# SCH_Cameron_PCB_2022-05-20.net
KiCad netlist of a schematic drawn in EasyEDA
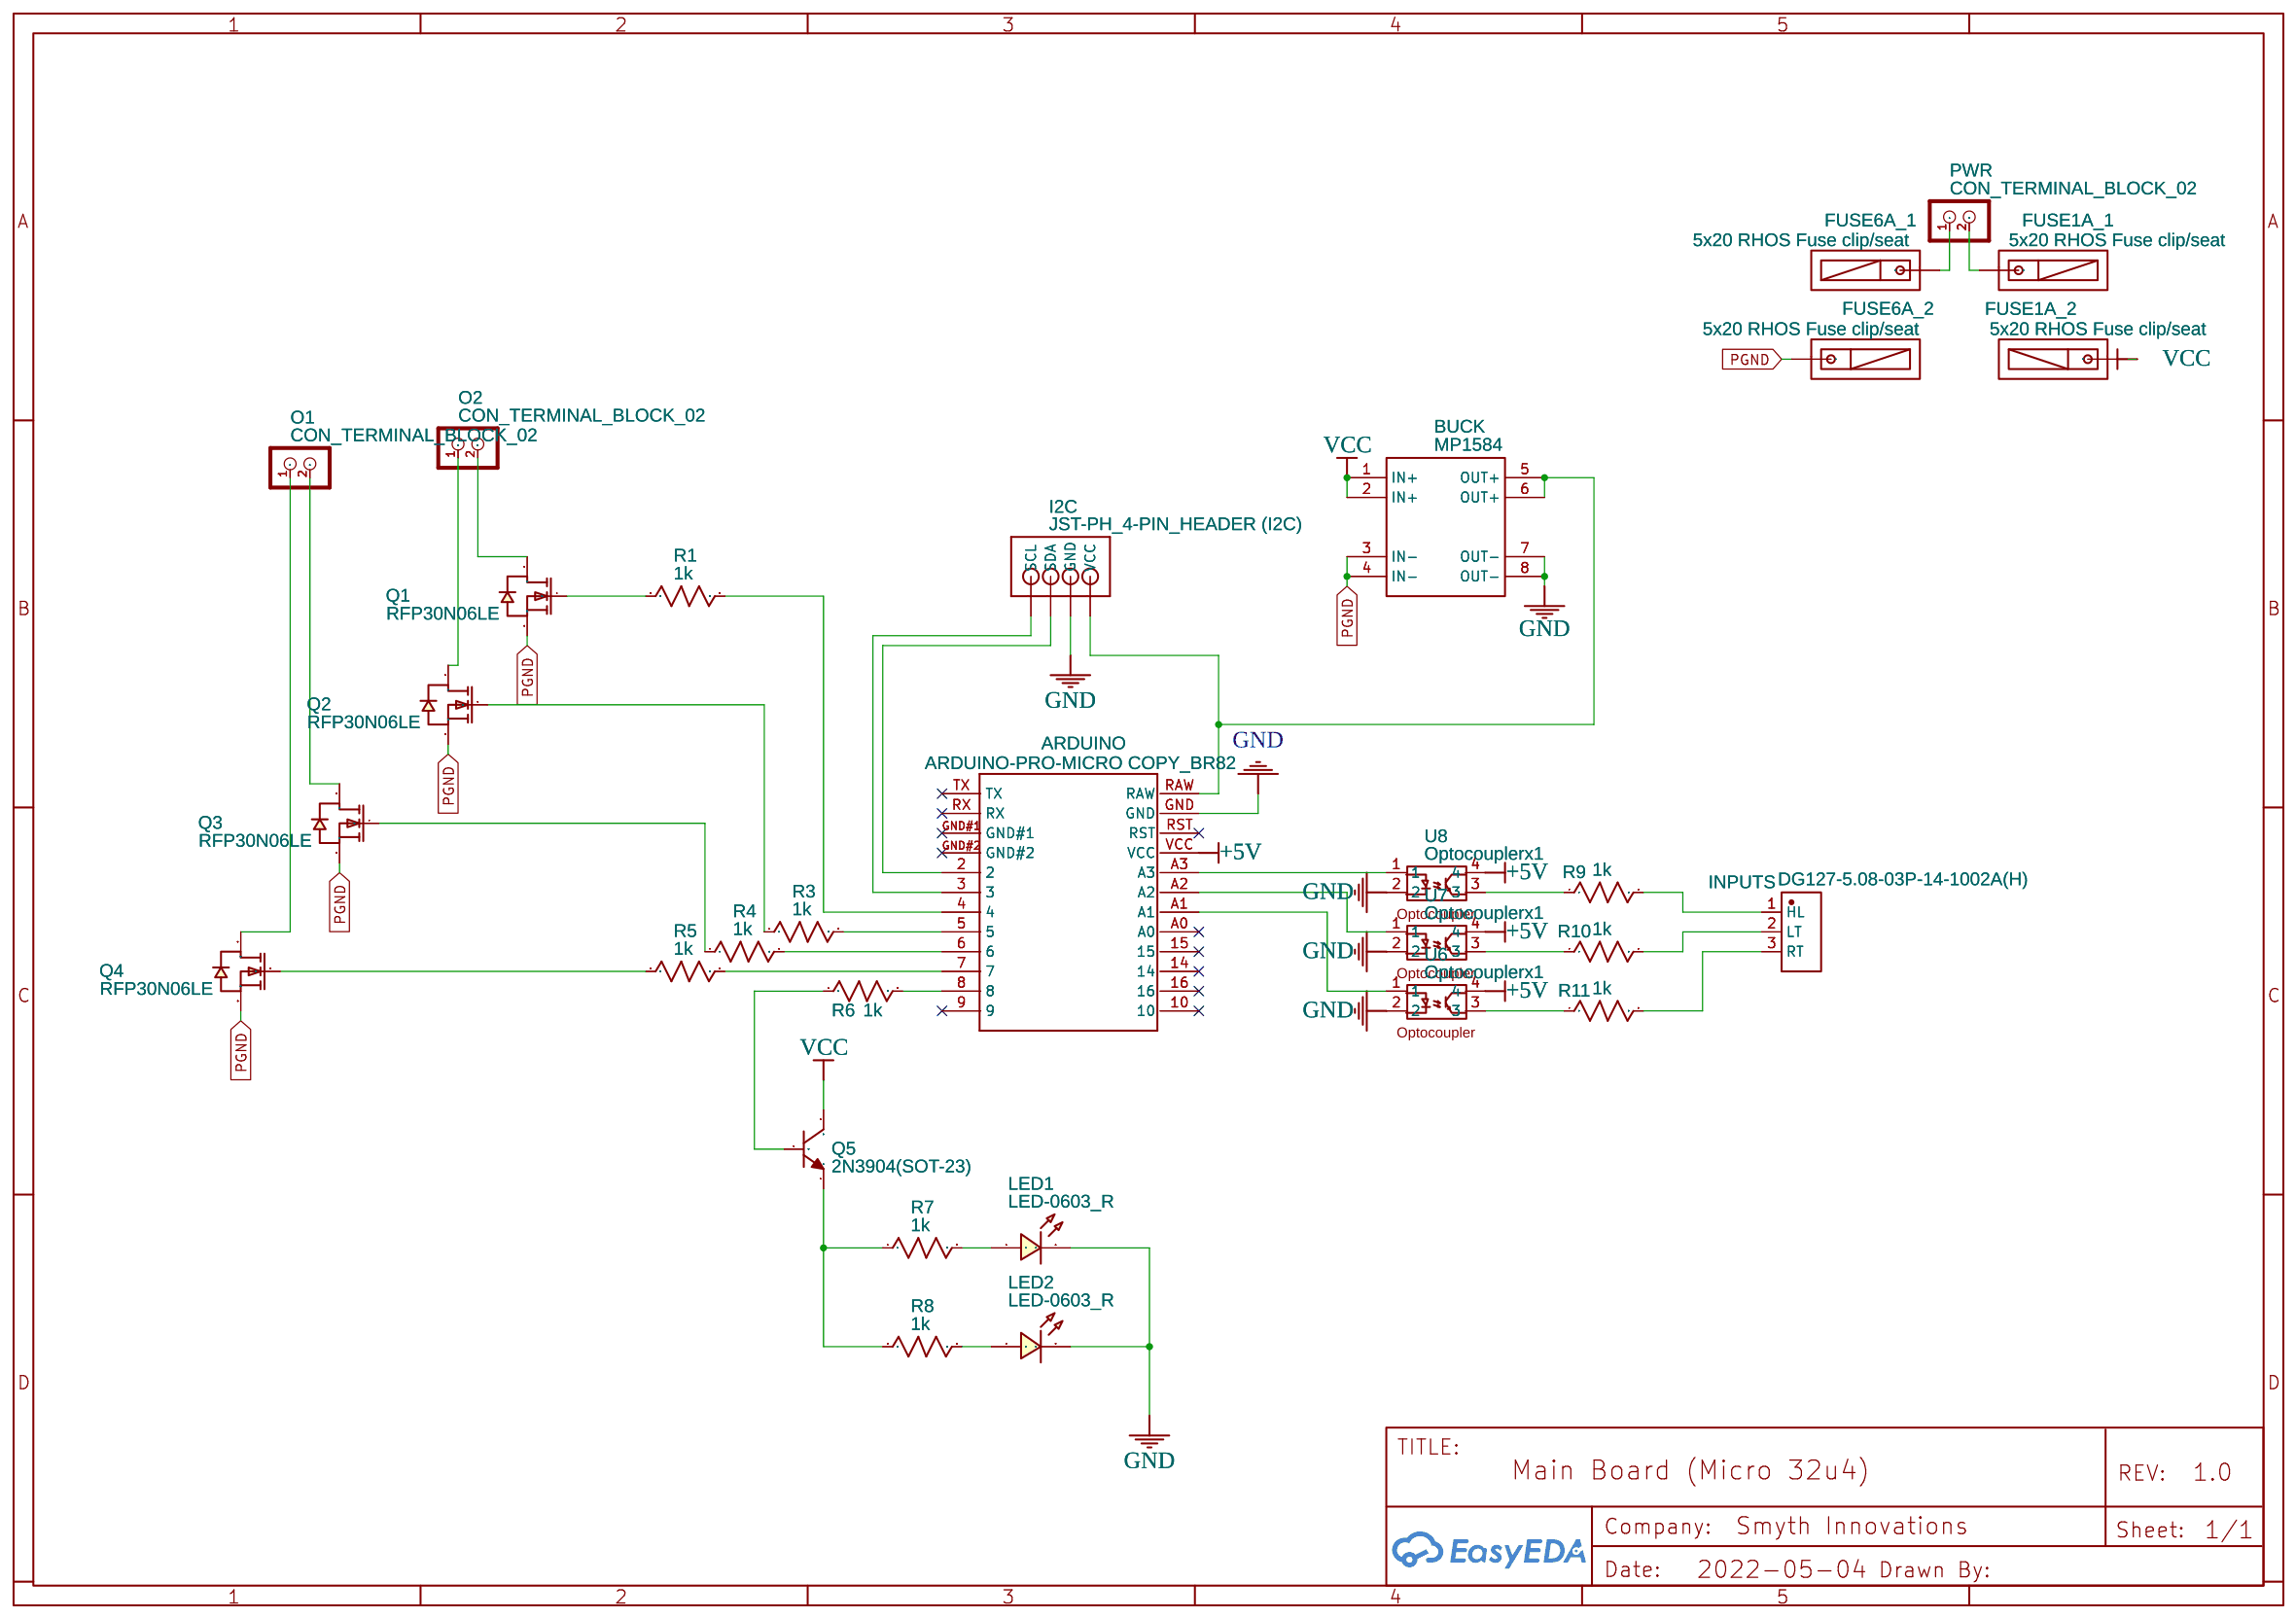
[diagram p0: schematic sheet]

(export (version "E")
  (design (tool "Eeschema 10.0.6"))
  (components
    (comp (ref "ARDUINO")
      (value "ARDUINO-PRO-MICRO COPY_BR82")
      (libsource (lib "") (part "ARDUINO-PRO-MICRO COPY_BR82"))
    )
    (comp (ref "BUCK") (value "MP1584") (libsource (lib "") (part "MP1584")))
    (comp (ref "FUSE1A_1")
      (value "5x20 RHOS Fuse clip/seat")
      (fields (field (name "BOM_Supplier Part") "C3130"))
      (libsource (lib "") (part "5x20 RHOS Fuse clip/seat_2"))
    )
    (comp (ref "FUSE1A_2")
      (value "5x20 RHOS Fuse clip/seat")
      (fields (field (name "BOM_Supplier Part") "C3130"))
      (libsource (lib "") (part "5x20 RHOS Fuse clip/seat_3"))
    )
    (comp (ref "FUSE6A_1")
      (value "5x20 RHOS Fuse clip/seat")
      (fields (field (name "BOM_Supplier Part") "C3130"))
      (libsource (lib "") (part "5x20 RHOS Fuse clip/seat_1"))
    )
    (comp (ref "FUSE6A_2")
      (value "5x20 RHOS Fuse clip/seat")
      (fields (field (name "BOM_Supplier Part") "C3130"))
      (libsource (lib "") (part "5x20 RHOS Fuse clip/seat"))
    )
    (comp (ref "I2C") (value "JST-PH_4-PIN_HEADER (I2C)") (libsource (lib "") (part "JST-PH_4-PIN_HEADER")))
    (comp (ref "INPUTS")
      (value "DG127-5.08-03P-14-1002A(H)")
      (fields (field (name "BOM_Supplier Part") "C669321"))
      (libsource (lib "") (part "DG127-5.08-03P-14-1002A(H)"))
    )
    (comp (ref "LED1")
      (value "LED-0603_R")
      (fields
        (field (name "BOM_Manufacturer Part") "19-217/R6C-AL1M2VY/3T")
        (field (name "BOM_Supplier Part") "C72044")
      )
      (libsource (lib "") (part "LED-0603_R"))
    )
    (comp (ref "LED2")
      (value "LED-0603_R")
      (fields
        (field (name "BOM_Manufacturer Part") "19-217/R6C-AL1M2VY/3T")
        (field (name "BOM_Supplier Part") "C72044")
      )
      (libsource (lib "") (part "LED-0603_R"))
    )
    (comp (ref "O1") (value "CON_TERMINAL_BLOCK_02") (libsource (lib "") (part "CON_TERMINAL_BLOCK_02")))
    (comp (ref "O2") (value "CON_TERMINAL_BLOCK_02") (libsource (lib "") (part "CON_TERMINAL_BLOCK_02")))
    (comp (ref "PWR") (value "CON_TERMINAL_BLOCK_02") (libsource (lib "") (part "CON_TERMINAL_BLOCK_02_1")))
    (comp (ref "Q1")
      (value "RFP30N06LE")
      (fields (field (name "BOM_Supplier Part") "C878812"))
      (libsource (lib "") (part "RFP30N06LE"))
    )
    (comp (ref "Q2")
      (value "RFP30N06LE")
      (fields (field (name "BOM_Supplier Part") "C878812"))
      (libsource (lib "") (part "RFP30N06LE"))
    )
    (comp (ref "Q3")
      (value "RFP30N06LE")
      (fields (field (name "BOM_Supplier Part") "C878812"))
      (libsource (lib "") (part "RFP30N06LE"))
    )
    (comp (ref "Q4")
      (value "RFP30N06LE")
      (fields (field (name "BOM_Supplier Part") "C878812"))
      (libsource (lib "") (part "RFP30N06LE"))
    )
    (comp (ref "Q5")
      (value "2N3904(SOT-23)")
      (fields
        (field (name "BOM_Manufacturer Part") "2n3904S-RTK/PS")
        (field (name "BOM_Supplier Part") "C18536")
      )
      (libsource (lib "") (part "2N3904(SOT-23)"))
    )
    (comp (ref "R1") (value "1k") (libsource (lib "") (part "R_AXIAL-0.3_US")))
    (comp (ref "R3") (value "1k") (libsource (lib "") (part "R_0603_US")))
    (comp (ref "R4") (value "1k") (libsource (lib "") (part "R_0603_US")))
    (comp (ref "R5") (value "1k") (libsource (lib "") (part "R_0603_US")))
    (comp (ref "R6") (value "1k") (libsource (lib "") (part "R_0603_US")))
    (comp (ref "R7") (value "1k") (libsource (lib "") (part "R_0603_US")))
    (comp (ref "R8") (value "1k") (libsource (lib "") (part "R_0603_US")))
    (comp (ref "R9") (value "1k") (libsource (lib "") (part "R_0603_US")))
    (comp (ref "R10") (value "1k") (libsource (lib "") (part "R_0603_US")))
    (comp (ref "R11") (value "1k") (libsource (lib "") (part "R_0603_US")))
    (comp (ref "U6")
      (value "Optocouplerx1")
      (fields (field (name "BOM_Manufacturer Part") "x"))
      (libsource (lib "") (part "Optocouplerx1"))
    )
    (comp (ref "U7")
      (value "Optocouplerx1")
      (fields (field (name "BOM_Manufacturer Part") "x"))
      (libsource (lib "") (part "Optocouplerx1"))
    )
    (comp (ref "U8")
      (value "Optocouplerx1")
      (fields (field (name "BOM_Manufacturer Part") "x"))
      (libsource (lib "") (part "Optocouplerx1"))
    )
  )
  (nets
    (net (code "1") (name "+5V") (class "Default")
      (node (ref "ARDUINO") (pin "VCC") (pinfunction "VCC_VCC") (pintype "bidirectional"))
      (node (ref "U6") (pin "4") (pinfunction "4_4") (pintype "unspecified"))
      (node (ref "U7") (pin "4") (pinfunction "4_4") (pintype "unspecified"))
      (node (ref "U8") (pin "4") (pinfunction "4_4") (pintype "unspecified"))
    )
    (net (code "2") (name "GND") (class "Default")
      (node (ref "ARDUINO") (pin "GND") (pinfunction "GND_GND") (pintype "bidirectional"))
      (node (ref "BUCK") (pin "7") (pinfunction "OUT-_7") (pintype "unspecified"))
      (node (ref "BUCK") (pin "8") (pinfunction "OUT-_8") (pintype "unspecified"))
      (node (ref "I2C") (pin "P3") (pinfunction "GND_P3") (pintype "unspecified"))
      (node (ref "LED1") (pin "2") (pinfunction "2_2") (pintype "unspecified"))
      (node (ref "LED2") (pin "2") (pinfunction "2_2") (pintype "unspecified"))
      (node (ref "U6") (pin "2") (pinfunction "2_2") (pintype "unspecified"))
      (node (ref "U7") (pin "2") (pinfunction "2_2") (pintype "unspecified"))
      (node (ref "U8") (pin "2") (pinfunction "2_2") (pintype "unspecified"))
    )
    (net (code "3") (name "Net-(ARDUINO-Pad4)") (class "Default")
      (node (ref "ARDUINO") (pin "4") (pinfunction "4_4") (pintype "bidirectional"))
      (node (ref "R1") (pin "2") (pinfunction "2_2") (pintype "unspecified"))
    )
    (net (code "4") (name "Net-(ARDUINO-Pad5)") (class "Default")
      (node (ref "ARDUINO") (pin "5") (pinfunction "5_5") (pintype "bidirectional"))
      (node (ref "R3") (pin "2") (pinfunction "2_2") (pintype "unspecified"))
    )
    (net (code "5") (name "Net-(ARDUINO-Pad6)") (class "Default")
      (node (ref "ARDUINO") (pin "6") (pinfunction "6_6") (pintype "bidirectional"))
      (node (ref "R4") (pin "2") (pinfunction "2_2") (pintype "unspecified"))
    )
    (net (code "6") (name "Net-(ARDUINO-Pad7)") (class "Default")
      (node (ref "ARDUINO") (pin "7") (pinfunction "7_7") (pintype "bidirectional"))
      (node (ref "R5") (pin "2") (pinfunction "2_2") (pintype "unspecified"))
    )
    (net (code "7") (name "Net-(ARDUINO-Pad8)") (class "Default")
      (node (ref "ARDUINO") (pin "8") (pinfunction "8_8") (pintype "bidirectional"))
      (node (ref "R6") (pin "2") (pinfunction "2_2") (pintype "unspecified"))
    )
    (net (code "8") (name "Net-(ARDUINO-PadA1)") (class "Default")
      (node (ref "ARDUINO") (pin "A1") (pinfunction "A1_A1") (pintype "bidirectional"))
      (node (ref "U6") (pin "1") (pinfunction "1_1") (pintype "unspecified"))
    )
    (net (code "9") (name "Net-(ARDUINO-PadA2)") (class "Default")
      (node (ref "ARDUINO") (pin "A2") (pinfunction "A2_A2") (pintype "bidirectional"))
      (node (ref "U7") (pin "1") (pinfunction "1_1") (pintype "unspecified"))
    )
    (net (code "10") (name "Net-(ARDUINO-PadA3)") (class "Default")
      (node (ref "ARDUINO") (pin "A3") (pinfunction "A3_A3") (pintype "bidirectional"))
      (node (ref "U8") (pin "1") (pinfunction "1_1") (pintype "unspecified"))
    )
    (net (code "11") (name "Net-(FUSE1A_1-Pad1)") (class "Default")
      (node (ref "FUSE1A_1") (pin "1") (pinfunction "1_1") (pintype "unspecified"))
      (node (ref "PWR") (pin "2") (pinfunction "2_2") (pintype "unspecified"))
    )
    (net (code "12") (name "Net-(FUSE6A_1-Pad1)") (class "Default")
      (node (ref "FUSE6A_1") (pin "1") (pinfunction "1_1") (pintype "unspecified"))
      (node (ref "PWR") (pin "1") (pinfunction "1_1") (pintype "unspecified"))
    )
    (net (code "13") (name "Net-(I2C-SCL)") (class "Default")
      (node (ref "ARDUINO") (pin "3") (pinfunction "3_3") (pintype "bidirectional"))
      (node (ref "I2C") (pin "P1") (pinfunction "SCL_P1") (pintype "unspecified"))
    )
    (net (code "14") (name "Net-(I2C-SDA)") (class "Default")
      (node (ref "ARDUINO") (pin "2") (pinfunction "2_2") (pintype "bidirectional"))
      (node (ref "I2C") (pin "P2") (pinfunction "SDA_P2") (pintype "unspecified"))
    )
    (net (code "15") (name "Net-(I2C-VCC)") (class "Default")
      (node (ref "ARDUINO") (pin "RAW") (pinfunction "RAW_RAW") (pintype "bidirectional"))
      (node (ref "BUCK") (pin "5") (pinfunction "OUT+_5") (pintype "unspecified"))
      (node (ref "BUCK") (pin "6") (pinfunction "OUT+_6") (pintype "unspecified"))
      (node (ref "I2C") (pin "P4") (pinfunction "VCC_P4") (pintype "unspecified"))
    )
    (net (code "16") (name "Net-(INPUTS-HL)") (class "Default")
      (node (ref "INPUTS") (pin "1") (pinfunction "HL_1") (pintype "unspecified"))
      (node (ref "R9") (pin "2") (pinfunction "2_2") (pintype "unspecified"))
    )
    (net (code "17") (name "Net-(INPUTS-LT)") (class "Default")
      (node (ref "INPUTS") (pin "2") (pinfunction "LT_2") (pintype "unspecified"))
      (node (ref "R10") (pin "2") (pinfunction "2_2") (pintype "unspecified"))
    )
    (net (code "18") (name "Net-(INPUTS-RT)") (class "Default")
      (node (ref "INPUTS") (pin "3") (pinfunction "RT_3") (pintype "unspecified"))
      (node (ref "R11") (pin "2") (pinfunction "2_2") (pintype "unspecified"))
    )
    (net (code "19") (name "Net-(LED1-Pad1)") (class "Default")
      (node (ref "LED1") (pin "1") (pinfunction "1_1") (pintype "unspecified"))
      (node (ref "R7") (pin "2") (pinfunction "2_2") (pintype "unspecified"))
    )
    (net (code "20") (name "Net-(LED2-Pad1)") (class "Default")
      (node (ref "LED2") (pin "1") (pinfunction "1_1") (pintype "unspecified"))
      (node (ref "R8") (pin "2") (pinfunction "2_2") (pintype "unspecified"))
    )
    (net (code "21") (name "Net-(Q1-D)") (class "Default")
      (node (ref "O2") (pin "2") (pinfunction "2_2") (pintype "unspecified"))
      (node (ref "Q1") (pin "2") (pinfunction "D_2") (pintype "unspecified"))
    )
    (net (code "22") (name "Net-(Q1-G)") (class "Default")
      (node (ref "Q1") (pin "1") (pinfunction "G_1") (pintype "unspecified"))
      (node (ref "R1") (pin "1") (pinfunction "1_1") (pintype "unspecified"))
    )
    (net (code "23") (name "Net-(Q2-D)") (class "Default")
      (node (ref "O2") (pin "1") (pinfunction "1_1") (pintype "unspecified"))
      (node (ref "Q2") (pin "2") (pinfunction "D_2") (pintype "unspecified"))
    )
    (net (code "24") (name "Net-(Q2-G)") (class "Default")
      (node (ref "Q2") (pin "1") (pinfunction "G_1") (pintype "unspecified"))
      (node (ref "R3") (pin "1") (pinfunction "1_1") (pintype "unspecified"))
    )
    (net (code "25") (name "Net-(Q3-D)") (class "Default")
      (node (ref "O1") (pin "2") (pinfunction "2_2") (pintype "unspecified"))
      (node (ref "Q3") (pin "2") (pinfunction "D_2") (pintype "unspecified"))
    )
    (net (code "26") (name "Net-(Q3-G)") (class "Default")
      (node (ref "Q3") (pin "1") (pinfunction "G_1") (pintype "unspecified"))
      (node (ref "R4") (pin "1") (pinfunction "1_1") (pintype "unspecified"))
    )
    (net (code "27") (name "Net-(Q4-D)") (class "Default")
      (node (ref "O1") (pin "1") (pinfunction "1_1") (pintype "unspecified"))
      (node (ref "Q4") (pin "2") (pinfunction "D_2") (pintype "unspecified"))
    )
    (net (code "28") (name "Net-(Q4-G)") (class "Default")
      (node (ref "Q4") (pin "1") (pinfunction "G_1") (pintype "unspecified"))
      (node (ref "R5") (pin "1") (pinfunction "1_1") (pintype "unspecified"))
    )
    (net (code "29") (name "Net-(Q5-B)") (class "Default")
      (node (ref "Q5") (pin "2") (pinfunction "B_2") (pintype "input"))
      (node (ref "R6") (pin "1") (pinfunction "1_1") (pintype "unspecified"))
    )
    (net (code "30") (name "Net-(Q5-E)") (class "Default")
      (node (ref "Q5") (pin "1") (pinfunction "E_1") (pintype "input"))
      (node (ref "R7") (pin "1") (pinfunction "1_1") (pintype "unspecified"))
      (node (ref "R8") (pin "1") (pinfunction "1_1") (pintype "unspecified"))
    )
    (net (code "31") (name "Net-(R9-Pad1)") (class "Default")
      (node (ref "R9") (pin "1") (pinfunction "1_1") (pintype "unspecified"))
      (node (ref "U8") (pin "3") (pinfunction "3_3") (pintype "unspecified"))
    )
    (net (code "32") (name "Net-(R10-Pad1)") (class "Default")
      (node (ref "R10") (pin "1") (pinfunction "1_1") (pintype "unspecified"))
      (node (ref "U7") (pin "3") (pinfunction "3_3") (pintype "unspecified"))
    )
    (net (code "33") (name "Net-(R11-Pad1)") (class "Default")
      (node (ref "R11") (pin "1") (pinfunction "1_1") (pintype "unspecified"))
      (node (ref "U6") (pin "3") (pinfunction "3_3") (pintype "unspecified"))
    )
    (net (code "34") (name "PGND") (class "Default")
      (node (ref "BUCK") (pin "3") (pinfunction "IN-_3") (pintype "unspecified"))
      (node (ref "BUCK") (pin "4") (pinfunction "IN-_4") (pintype "unspecified"))
      (node (ref "FUSE6A_2") (pin "1") (pinfunction "1_1") (pintype "unspecified"))
      (node (ref "Q1") (pin "3") (pinfunction "S_3") (pintype "unspecified"))
      (node (ref "Q2") (pin "3") (pinfunction "S_3") (pintype "unspecified"))
      (node (ref "Q3") (pin "3") (pinfunction "S_3") (pintype "unspecified"))
      (node (ref "Q4") (pin "3") (pinfunction "S_3") (pintype "unspecified"))
    )
    (net (code "35") (name "VCC") (class "Default")
      (node (ref "BUCK") (pin "1") (pinfunction "IN+_1") (pintype "unspecified"))
      (node (ref "BUCK") (pin "2") (pinfunction "IN+_2") (pintype "unspecified"))
      (node (ref "FUSE1A_2") (pin "1") (pinfunction "1_1") (pintype "unspecified"))
      (node (ref "Q5") (pin "3") (pinfunction "C_3") (pintype "input"))
    )
    (net (code "36") (name "unconnected-(ARDUINO-Pad9)") (class "Default")
      (node (ref "ARDUINO") (pin "9") (pinfunction "9_9") (pintype "bidirectional+no_connect"))
    )
    (net (code "37") (name "unconnected-(ARDUINO-Pad10)") (class "Default")
      (node (ref "ARDUINO") (pin "10") (pinfunction "10_10") (pintype "bidirectional+no_connect"))
    )
    (net (code "38") (name "unconnected-(ARDUINO-Pad14)") (class "Default")
      (node (ref "ARDUINO") (pin "14") (pinfunction "14_14") (pintype "bidirectional+no_connect"))
    )
    (net (code "39") (name "unconnected-(ARDUINO-Pad15)") (class "Default")
      (node (ref "ARDUINO") (pin "15") (pinfunction "15_15") (pintype "bidirectional+no_connect"))
    )
    (net (code "40") (name "unconnected-(ARDUINO-Pad16)") (class "Default")
      (node (ref "ARDUINO") (pin "16") (pinfunction "16_16") (pintype "bidirectional+no_connect"))
    )
    (net (code "41") (name "unconnected-(ARDUINO-PadA0)") (class "Default")
      (node (ref "ARDUINO") (pin "A0") (pinfunction "A0_A0") (pintype "bidirectional+no_connect"))
    )
    (net (code "42") (name "unconnected-(ARDUINO-PadGND#1)") (class "Default")
      (node (ref "ARDUINO") (pin "GND#1") (pinfunction "GND#1_GND#1") (pintype "bidirectional+no_connect"))
    )
    (net (code "43") (name "unconnected-(ARDUINO-PadGND#2)") (class "Default")
      (node (ref "ARDUINO") (pin "GND#2") (pinfunction "GND#2_GND#2") (pintype "bidirectional+no_connect"))
    )
    (net (code "44") (name "unconnected-(ARDUINO-PadRST)") (class "Default")
      (node (ref "ARDUINO") (pin "RST") (pinfunction "RST_RST") (pintype "bidirectional+no_connect"))
    )
    (net (code "45") (name "unconnected-(ARDUINO-PadRX)") (class "Default")
      (node (ref "ARDUINO") (pin "RX") (pinfunction "RX_RX") (pintype "bidirectional+no_connect"))
    )
    (net (code "46") (name "unconnected-(ARDUINO-PadTX)") (class "Default")
      (node (ref "ARDUINO") (pin "TX") (pinfunction "TX_TX") (pintype "bidirectional+no_connect"))
    )
  )
)
